# Platine_L6470.net
KiCad netlist of a schematic drawn in EAGLE
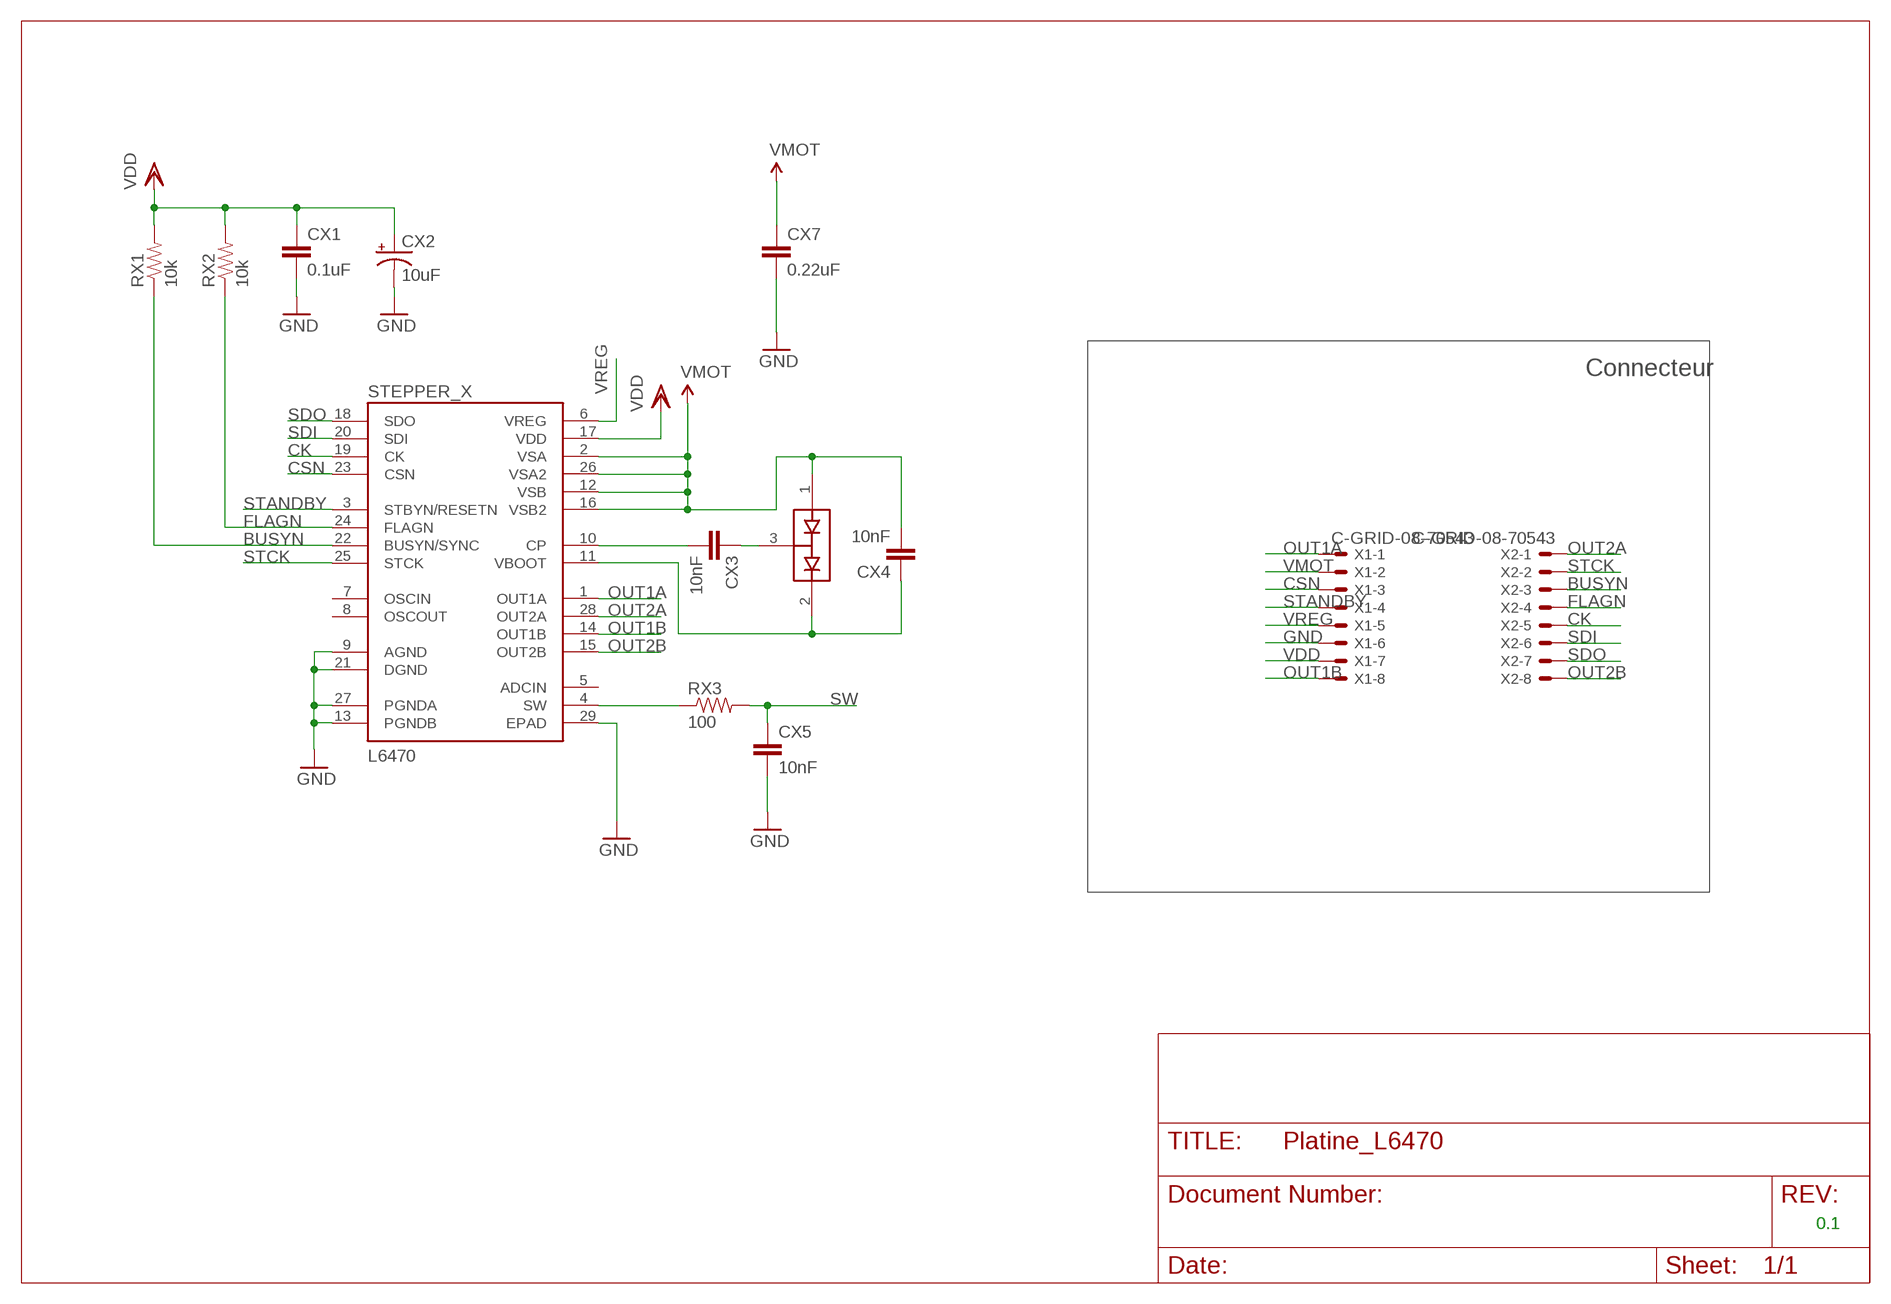
[diagram p0: schematic, sheet 1]

(export (version "E")
  (design (tool "Eeschema 10.0.6"))
  (components
    (comp (ref "CX1")
      (value "0.1uF")
      (footprint "eagle-import:0402-CAP")
      (libsource (lib "eagle-import") (part "CAP0402-CAP"))
    )
    (comp (ref "CX2")
      (value "10uF")
      (footprint "eagle-import:EIA3216")
      (libsource (lib "eagle-import") (part "CAP_POL1206"))
    )
    (comp (ref "CX3")
      (value "10nF")
      (footprint "eagle-import:0402-CAP")
      (libsource (lib "eagle-import") (part "CAP0402-CAP"))
    )
    (comp (ref "CX4")
      (value "10nF")
      (footprint "eagle-import:0402-CAP")
      (libsource (lib "eagle-import") (part "CAP0402-CAP"))
    )
    (comp (ref "CX5")
      (value "10nF")
      (footprint "eagle-import:0402-CAP")
      (libsource (lib "eagle-import") (part "CAP0402-CAP"))
    )
    (comp (ref "CX7")
      (value "0.22uF")
      (footprint "eagle-import:0603-CAP")
      (libsource (lib "eagle-import") (part "CAP0603-CAP"))
    )
    (comp (ref "DX1")
      (value "BAV99")
      (footprint "eagle-import:SOT23")
      (libsource (lib "eagle-import") (part "BAV99"))
    )
    (comp (ref "RX1")
      (value "10k")
      (footprint "eagle-import:0402-RES")
      (libsource (lib "eagle-import") (part "RESISTOR0402-RES"))
    )
    (comp (ref "RX2")
      (value "10k")
      (footprint "eagle-import:0402-RES")
      (libsource (lib "eagle-import") (part "RESISTOR0402-RES"))
    )
    (comp (ref "RX3")
      (value "100")
      (footprint "eagle-import:0402-RES")
      (libsource (lib "eagle-import") (part "RESISTOR0402-RES"))
    )
    (comp (ref "STEPPER_X")
      (value "L6470")
      (footprint "eagle-import:HTSSOP28")
      (libsource (lib "eagle-import") (part "L6470"))
    )
    (comp (ref "X1")
      (value "C-GRID-08-70543")
      (footprint "eagle-import:70543-08")
      (libsource (lib "eagle-import") (part "C-GRID-08-70543"))
    )
    (comp (ref "X2")
      (value "C-GRID-08-70543")
      (footprint "eagle-import:70543-08")
      (libsource (lib "eagle-import") (part "C-GRID-08-70543"))
    )
  )
  (nets
    (net (code "1") (name "/BUSYN") (class "Default")
      (node (ref "RX1") (pin "1") (pinfunction "1_1") (pintype "passive"))
      (node (ref "STEPPER_X") (pin "22") (pinfunction "BUSYN/SYNC_22") (pintype "bidirectional"))
      (node (ref "X2") (pin "3") (pinfunction "S_3") (pintype "passive"))
    )
    (net (code "2") (name "/CK") (class "Default")
      (node (ref "STEPPER_X") (pin "19") (pinfunction "CK_19") (pintype "bidirectional"))
      (node (ref "X2") (pin "5") (pinfunction "S_5") (pintype "passive"))
    )
    (net (code "3") (name "/CSN") (class "Default")
      (node (ref "STEPPER_X") (pin "23") (pinfunction "CSN_23") (pintype "bidirectional"))
      (node (ref "X1") (pin "3") (pinfunction "S_3") (pintype "passive"))
    )
    (net (code "4") (name "/FLAGN") (class "Default")
      (node (ref "RX2") (pin "1") (pinfunction "1_1") (pintype "passive"))
      (node (ref "STEPPER_X") (pin "24") (pinfunction "FLAGN_24") (pintype "bidirectional"))
      (node (ref "X2") (pin "4") (pinfunction "S_4") (pintype "passive"))
    )
    (net (code "5") (name "/OUT1A") (class "Default")
      (node (ref "STEPPER_X") (pin "1") (pinfunction "OUT1A_1") (pintype "bidirectional"))
      (node (ref "X1") (pin "1") (pinfunction "S_1") (pintype "passive"))
    )
    (net (code "6") (name "/OUT1B") (class "Default")
      (node (ref "STEPPER_X") (pin "14") (pinfunction "OUT1B_14") (pintype "bidirectional"))
      (node (ref "X1") (pin "8") (pinfunction "S_8") (pintype "passive"))
    )
    (net (code "7") (name "/OUT2A") (class "Default")
      (node (ref "STEPPER_X") (pin "28") (pinfunction "OUT2A_28") (pintype "bidirectional"))
      (node (ref "X2") (pin "1") (pinfunction "S_1") (pintype "passive"))
    )
    (net (code "8") (name "/OUT2B") (class "Default")
      (node (ref "STEPPER_X") (pin "15") (pinfunction "OUT2B_15") (pintype "bidirectional"))
      (node (ref "X2") (pin "8") (pinfunction "S_8") (pintype "passive"))
    )
    (net (code "9") (name "/SDI") (class "Default")
      (node (ref "STEPPER_X") (pin "20") (pinfunction "SDI_20") (pintype "bidirectional"))
      (node (ref "X2") (pin "6") (pinfunction "S_6") (pintype "passive"))
    )
    (net (code "10") (name "/SDO") (class "Default")
      (node (ref "STEPPER_X") (pin "18") (pinfunction "SDO_18") (pintype "bidirectional"))
      (node (ref "X2") (pin "7") (pinfunction "S_7") (pintype "passive"))
    )
    (net (code "11") (name "/STANDBY") (class "Default")
      (node (ref "STEPPER_X") (pin "3") (pinfunction "STBYN/RESETN_3") (pintype "bidirectional"))
      (node (ref "X1") (pin "4") (pinfunction "S_4") (pintype "passive"))
    )
    (net (code "12") (name "/STCK") (class "Default")
      (node (ref "STEPPER_X") (pin "25") (pinfunction "STCK_25") (pintype "bidirectional"))
      (node (ref "X2") (pin "2") (pinfunction "S_2") (pintype "passive"))
    )
    (net (code "13") (name "/SW") (class "Default")
      (node (ref "CX5") (pin "1") (pinfunction "1_1") (pintype "passive"))
      (node (ref "RX3") (pin "2") (pinfunction "2_2") (pintype "passive"))
    )
    (net (code "14") (name "/VREG") (class "Default")
      (node (ref "STEPPER_X") (pin "6") (pinfunction "VREG_6") (pintype "bidirectional"))
      (node (ref "X1") (pin "5") (pinfunction "S_5") (pintype "passive"))
    )
    (net (code "15") (name "GND") (class "Default")
      (node (ref "CX1") (pin "2") (pinfunction "2_2") (pintype "passive"))
      (node (ref "CX2") (pin "C") (pinfunction "-_C") (pintype "passive"))
      (node (ref "CX5") (pin "2") (pinfunction "2_2") (pintype "passive"))
      (node (ref "CX7") (pin "2") (pinfunction "2_2") (pintype "passive"))
      (node (ref "STEPPER_X") (pin "13") (pinfunction "PGNDB_13") (pintype "bidirectional"))
      (node (ref "STEPPER_X") (pin "21") (pinfunction "DGND_21") (pintype "bidirectional"))
      (node (ref "STEPPER_X") (pin "27") (pinfunction "PGNDA_27") (pintype "bidirectional"))
      (node (ref "STEPPER_X") (pin "29") (pinfunction "EPAD_29") (pintype "bidirectional"))
      (node (ref "STEPPER_X") (pin "9") (pinfunction "AGND_9") (pintype "bidirectional"))
      (node (ref "X1") (pin "6") (pinfunction "S_6") (pintype "passive"))
    )
    (net (code "16") (name "Net-(DX1-C2)") (class "Default")
      (node (ref "CX4") (pin "1") (pinfunction "1_1") (pintype "passive"))
      (node (ref "DX1") (pin "2") (pinfunction "C2_2") (pintype "bidirectional"))
      (node (ref "STEPPER_X") (pin "11") (pinfunction "VBOOT_11") (pintype "bidirectional"))
    )
    (net (code "17") (name "Net-(DX1-COM)") (class "Default")
      (node (ref "CX3") (pin "1") (pinfunction "1_1") (pintype "passive"))
      (node (ref "DX1") (pin "3") (pinfunction "COM_3") (pintype "bidirectional"))
    )
    (net (code "18") (name "Net-(STEPPER_X-CP)") (class "Default")
      (node (ref "CX3") (pin "2") (pinfunction "2_2") (pintype "passive"))
      (node (ref "STEPPER_X") (pin "10") (pinfunction "CP_10") (pintype "bidirectional"))
    )
    (net (code "19") (name "Net-(STEPPER_X-SW)") (class "Default")
      (node (ref "RX3") (pin "1") (pinfunction "1_1") (pintype "passive"))
      (node (ref "STEPPER_X") (pin "4") (pinfunction "SW_4") (pintype "bidirectional"))
    )
    (net (code "20") (name "VDD") (class "Default")
      (node (ref "CX1") (pin "1") (pinfunction "1_1") (pintype "passive"))
      (node (ref "CX2") (pin "A") (pinfunction "+_A") (pintype "passive"))
      (node (ref "RX1") (pin "2") (pinfunction "2_2") (pintype "passive"))
      (node (ref "RX2") (pin "2") (pinfunction "2_2") (pintype "passive"))
      (node (ref "STEPPER_X") (pin "17") (pinfunction "VDD_17") (pintype "bidirectional"))
      (node (ref "X1") (pin "7") (pinfunction "S_7") (pintype "passive"))
    )
    (net (code "21") (name "VMOT") (class "Default")
      (node (ref "CX4") (pin "2") (pinfunction "2_2") (pintype "passive"))
      (node (ref "CX7") (pin "1") (pinfunction "1_1") (pintype "passive"))
      (node (ref "DX1") (pin "1") (pinfunction "A1_1") (pintype "bidirectional"))
      (node (ref "STEPPER_X") (pin "12") (pinfunction "VSB_12") (pintype "bidirectional"))
      (node (ref "STEPPER_X") (pin "16") (pinfunction "VSB2_16") (pintype "bidirectional"))
      (node (ref "STEPPER_X") (pin "2") (pinfunction "VSA_2") (pintype "bidirectional"))
      (node (ref "STEPPER_X") (pin "26") (pinfunction "VSA2_26") (pintype "bidirectional"))
      (node (ref "X1") (pin "2") (pinfunction "S_2") (pintype "passive"))
    )
    (net (code "22") (name "unconnected-(STEPPER_X-ADCIN-Pad5)") (class "Default")
      (node (ref "STEPPER_X") (pin "5") (pinfunction "ADCIN_5") (pintype "bidirectional"))
    )
    (net (code "23") (name "unconnected-(STEPPER_X-OSCIN-Pad7)") (class "Default")
      (node (ref "STEPPER_X") (pin "7") (pinfunction "OSCIN_7") (pintype "bidirectional"))
    )
    (net (code "24") (name "unconnected-(STEPPER_X-OSCOUT-Pad8)") (class "Default")
      (node (ref "STEPPER_X") (pin "8") (pinfunction "OSCOUT_8") (pintype "bidirectional"))
    )
  )
)
